# SparkFun_Cryptographic_Co-processor_ATEC.net
KiCad netlist of a schematic drawn in EAGLE
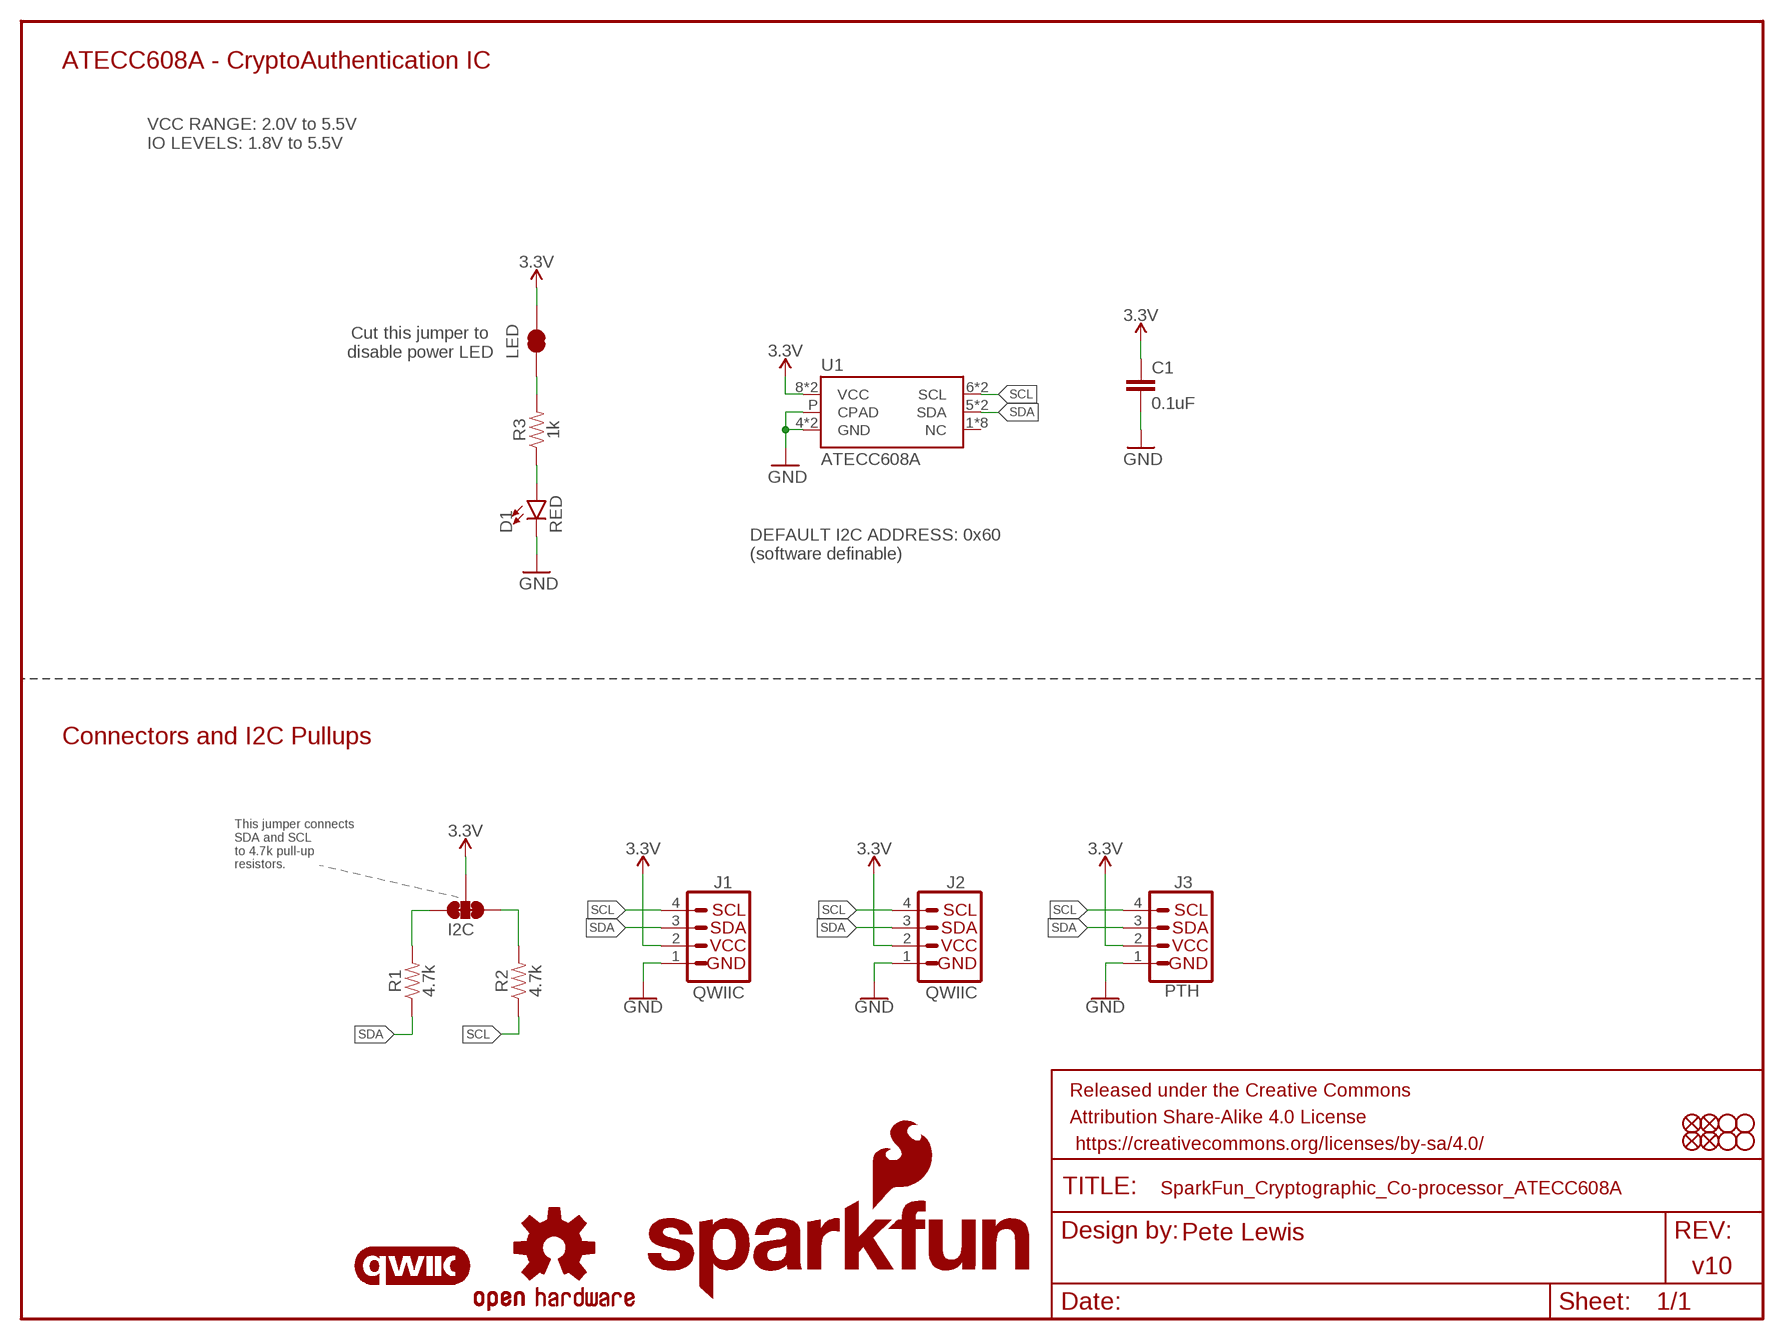
[diagram p0: schematic, sheet 1]

(export (version "E")
  (design (tool "Eeschema 10.0.6"))
  (components
    (comp (ref "C1")
      (value "0.1uF")
      (footprint "eagle-import:0603")
      (libsource (lib "eagle-import") (part "0.1UF-0603-25V-(+80/-20%)"))
    )
    (comp (ref "D1")
      (value "RED")
      (footprint "eagle-import:LED-0603")
      (libsource (lib "eagle-import") (part "LED-RED0603"))
    )
    (comp (ref "FD1")
      (value "FIDUCIAL1X2")
      (footprint "eagle-import:FIDUCIAL-1X2")
      (libsource (lib "eagle-import") (part "FIDUCIAL1X2"))
    )
    (comp (ref "FD2")
      (value "FIDUCIAL1X2")
      (footprint "eagle-import:FIDUCIAL-1X2")
      (libsource (lib "eagle-import") (part "FIDUCIAL1X2"))
    )
    (comp (ref "FD3")
      (value "FIDUCIAL1X2")
      (footprint "eagle-import:FIDUCIAL-1X2")
      (libsource (lib "eagle-import") (part "FIDUCIAL1X2"))
    )
    (comp (ref "FD4")
      (value "FIDUCIAL1X2")
      (footprint "eagle-import:FIDUCIAL-1X2")
      (libsource (lib "eagle-import") (part "FIDUCIAL1X2"))
    )
    (comp (ref "FRAME1")
      (value "FRAME-LETTER")
      (footprint "eagle-import:CREATIVE_COMMONS")
      (libsource (lib "eagle-import") (part "FRAME-LETTER"))
    )
    (comp (ref "H1")
      (value "STAND-OFF")
      (footprint "eagle-import:STAND-OFF")
      (libsource (lib "eagle-import") (part "STAND-OFF"))
    )
    (comp (ref "H2")
      (value "STAND-OFF")
      (footprint "eagle-import:STAND-OFF")
      (libsource (lib "eagle-import") (part "STAND-OFF"))
    )
    (comp (ref "H3")
      (value "STAND-OFF")
      (footprint "eagle-import:STAND-OFF")
      (libsource (lib "eagle-import") (part "STAND-OFF"))
    )
    (comp (ref "H4")
      (value "STAND-OFF")
      (footprint "eagle-import:STAND-OFF")
      (libsource (lib "eagle-import") (part "STAND-OFF"))
    )
    (comp (ref "I2C")
      (value "JUMPER-SMT_3_2-NC_TRACE_SILK")
      (footprint "eagle-import:SMT-JUMPER_3_2-NC_TRACE_SILK")
      (libsource (lib "eagle-import") (part "JUMPER-SMT_3_2-NC_TRACE_SILK"))
    )
    (comp (ref "J1")
      (value "QWIIC")
      (footprint "eagle-import:JST04_1MM_RA")
      (libsource (lib "eagle-import") (part "I2C_STANDARDQWIIC"))
    )
    (comp (ref "J2")
      (value "QWIIC")
      (footprint "eagle-import:JST04_1MM_RA")
      (libsource (lib "eagle-import") (part "I2C_STANDARDQWIIC"))
    )
    (comp (ref "J3")
      (value "PTH")
      (footprint "eagle-import:1X04_NO_SILK")
      (libsource (lib "eagle-import") (part "I2C_STANDARD_NO_SILK"))
    )
    (comp (ref "LED")
      (value "JUMPER-SMT_2_NC_TRACE_SILK")
      (footprint "eagle-import:SMT-JUMPER_2_NC_TRACE_SILK")
      (libsource (lib "eagle-import") (part "JUMPER-SMT_2_NC_TRACE_SILK"))
    )
    (comp (ref "LOGO1")
      (value "SFE_LOGO_NAME_FLAME.1_INCH")
      (footprint "eagle-import:SFE_LOGO_NAME_FLAME_.1")
      (libsource (lib "eagle-import") (part "SFE_LOGO_NAME_FLAME.1_INCH"))
    )
    (comp (ref "LOGO3")
      (value "QWIIC_LOGO_4MM")
      (footprint "eagle-import:QWIIC_4MM")
      (libsource (lib "eagle-import") (part "QWIIC_LOGO_4MM"))
    )
    (comp (ref "LOGO4")
      (value "OSHW-LOGOS")
      (footprint "eagle-import:OSHW-LOGO-S")
      (libsource (lib "eagle-import") (part "OSHW-LOGOS"))
    )
    (comp (ref "R1")
      (value "4.7k")
      (footprint "eagle-import:0603")
      (libsource (lib "eagle-import") (part "4.7KOHM-0603-1/10W-1%"))
    )
    (comp (ref "R2")
      (value "4.7k")
      (footprint "eagle-import:0603")
      (libsource (lib "eagle-import") (part "4.7KOHM-0603-1/10W-1%"))
    )
    (comp (ref "R3")
      (value "1k")
      (footprint "eagle-import:0603")
      (libsource (lib "eagle-import") (part "1KOHM-0603-1/10W-1%"))
    )
    (comp (ref "U1")
      (value "ATECC608A")
      (footprint "eagle-import:DUAL_UDFN_2X3MM_SOIC-8")
      (libsource (lib "eagle-import") (part "ATECC608ADUAL_PACKAGE_UDFN_SOIC-8"))
    )
  )
  (nets
    (net (code "1") (name "3.3V") (class "Default")
      (node (ref "C1") (pin "1") (pinfunction "1_1") (pintype "passive"))
      (node (ref "I2C") (pin "2") (pinfunction "2_2") (pintype "passive"))
      (node (ref "J1") (pin "2") (pinfunction "2_2") (pintype "power_in"))
      (node (ref "J2") (pin "2") (pinfunction "2_2") (pintype "power_in"))
      (node (ref "J3") (pin "2") (pinfunction "2_2") (pintype "power_in"))
      (node (ref "LED") (pin "2") (pinfunction "2_2") (pintype "passive"))
      (node (ref "U1") (pin "8") (pinfunction "VCC_8") (pintype "power_in"))
      (node (ref "U1") (pin "8S") (pinfunction "VCC_8S") (pintype "power_in"))
    )
    (net (code "2") (name "GND") (class "Default")
      (node (ref "C1") (pin "2") (pinfunction "2_2") (pintype "passive"))
      (node (ref "D1") (pin "C") (pinfunction "C_C") (pintype "passive"))
      (node (ref "J1") (pin "1") (pinfunction "1_1") (pintype "power_in"))
      (node (ref "J2") (pin "1") (pinfunction "1_1") (pintype "power_in"))
      (node (ref "J3") (pin "1") (pinfunction "1_1") (pintype "power_in"))
      (node (ref "U1") (pin "4") (pinfunction "GND_4") (pintype "power_in"))
      (node (ref "U1") (pin "4S") (pinfunction "GND_4S") (pintype "power_in"))
      (node (ref "U1") (pin "P") (pinfunction "CPAD_P") (pintype "power_in"))
    )
    (net (code "3") (name "Net-(D1-PadA)") (class "Default")
      (node (ref "D1") (pin "A") (pinfunction "A_A") (pintype "passive"))
      (node (ref "R3") (pin "1") (pinfunction "1_1") (pintype "passive"))
    )
    (net (code "4") (name "Net-(I2C-Pad1)") (class "Default")
      (node (ref "I2C") (pin "1") (pinfunction "1_1") (pintype "passive"))
      (node (ref "R2") (pin "2") (pinfunction "2_2") (pintype "passive"))
    )
    (net (code "5") (name "Net-(I2C-Pad3)") (class "Default")
      (node (ref "I2C") (pin "3") (pinfunction "3_3") (pintype "passive"))
      (node (ref "R1") (pin "2") (pinfunction "2_2") (pintype "passive"))
    )
    (net (code "6") (name "Net-(LED-Pad1)") (class "Default")
      (node (ref "LED") (pin "1") (pinfunction "1_1") (pintype "passive"))
      (node (ref "R3") (pin "2") (pinfunction "2_2") (pintype "passive"))
    )
    (net (code "7") (name "SCL") (class "Default")
      (node (ref "J1") (pin "4") (pinfunction "4_4") (pintype "passive"))
      (node (ref "J2") (pin "4") (pinfunction "4_4") (pintype "passive"))
      (node (ref "J3") (pin "4") (pinfunction "4_4") (pintype "passive"))
      (node (ref "R2") (pin "1") (pinfunction "1_1") (pintype "passive"))
      (node (ref "U1") (pin "6") (pinfunction "SCL_6") (pintype "bidirectional"))
      (node (ref "U1") (pin "6S") (pinfunction "SCL_6S") (pintype "bidirectional"))
    )
    (net (code "8") (name "SDA") (class "Default")
      (node (ref "J1") (pin "3") (pinfunction "3_3") (pintype "passive"))
      (node (ref "J2") (pin "3") (pinfunction "3_3") (pintype "passive"))
      (node (ref "J3") (pin "3") (pinfunction "3_3") (pintype "passive"))
      (node (ref "R1") (pin "1") (pinfunction "1_1") (pintype "passive"))
      (node (ref "U1") (pin "5") (pinfunction "SDA_5") (pintype "bidirectional"))
      (node (ref "U1") (pin "5S") (pinfunction "SDA_5S") (pintype "bidirectional"))
    )
    (net (code "9") (name "unconnected-(U1-NC-Pad1)") (class "Default")
      (node (ref "U1") (pin "1") (pinfunction "NC_1") (pintype "no_connect"))
    )
    (net (code "10") (name "unconnected-(U1-NC-Pad1S)") (class "Default")
      (node (ref "U1") (pin "1S") (pinfunction "NC_1S") (pintype "no_connect"))
    )
    (net (code "11") (name "unconnected-(U1-NC-Pad2)") (class "Default")
      (node (ref "U1") (pin "2") (pinfunction "NC_2") (pintype "no_connect"))
    )
    (net (code "12") (name "unconnected-(U1-NC-Pad2S)") (class "Default")
      (node (ref "U1") (pin "2S") (pinfunction "NC_2S") (pintype "no_connect"))
    )
    (net (code "13") (name "unconnected-(U1-NC-Pad3)") (class "Default")
      (node (ref "U1") (pin "3") (pinfunction "NC_3") (pintype "no_connect"))
    )
    (net (code "14") (name "unconnected-(U1-NC-Pad3S)") (class "Default")
      (node (ref "U1") (pin "3S") (pinfunction "NC_3S") (pintype "no_connect"))
    )
    (net (code "15") (name "unconnected-(U1-NC-Pad7)") (class "Default")
      (node (ref "U1") (pin "7") (pinfunction "NC_7") (pintype "no_connect"))
    )
    (net (code "16") (name "unconnected-(U1-NC-Pad7S)") (class "Default")
      (node (ref "U1") (pin "7S") (pinfunction "NC_7S") (pintype "no_connect"))
    )
  )
)
